# RF.net
KiCad netlist of a schematic drawn in Altium Designer
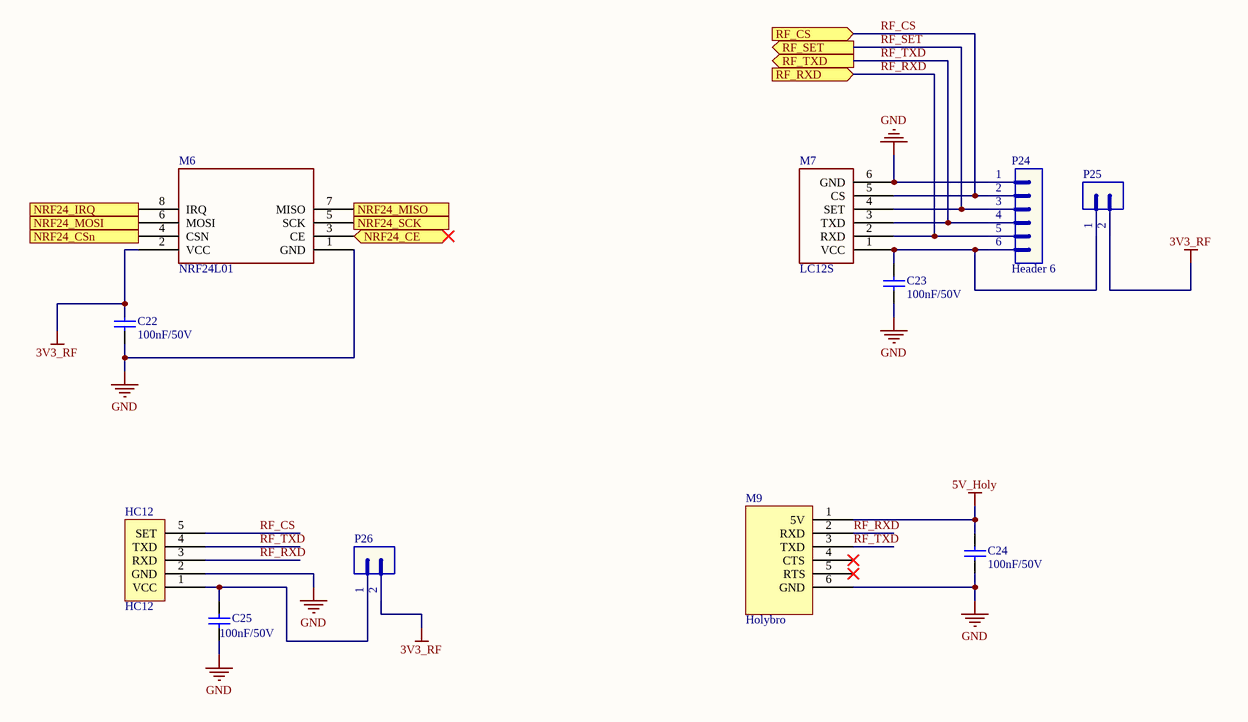
[diagram p0: RF.SchDoc]

(export (version "E")
  (design (tool "Eeschema 10.0.6"))
  (components
    (comp (ref "C22")
      (value "100nF/50V")
      (footprint "CAP-SM-0805")
      (description "CAP CER 0.1UF 50V Y5V 0805")
      (fields
        (field (name "MANUFACTURER") "Samsung Electro-Mechanics")
        (field (name "MANUFACTURER PART NUMBER") "CL21F104ZBCNNNC")
      )
      (libsource (lib "PIF_ROBOT") (part "Cap-100nF-50V-0805"))
    )
    (comp (ref "C23")
      (value "100nF/50V")
      (footprint "CAP-SM-0805")
      (description "CAP CER 0.1UF 50V Y5V 0805")
      (fields
        (field (name "MANUFACTURER") "Samsung Electro-Mechanics")
        (field (name "MANUFACTURER PART NUMBER") "CL21F104ZBCNNNC")
      )
      (libsource (lib "PIF_ROBOT") (part "Cap-100nF-50V-0805"))
    )
    (comp (ref "C24")
      (value "100nF/50V")
      (footprint "CAP-SM-0805")
      (description "CAP CER 0.1UF 50V Y5V 0805")
      (fields
        (field (name "MANUFACTURER") "Samsung Electro-Mechanics")
        (field (name "MANUFACTURER PART NUMBER") "CL21F104ZBCNNNC")
      )
      (libsource (lib "PIF_ROBOT") (part "Cap-100nF-50V-0805"))
    )
    (comp (ref "C25")
      (value "100nF/50V")
      (footprint "CAP-SM-0805")
      (description "CAP CER 0.1UF 50V Y5V 0805")
      (fields
        (field (name "MANUFACTURER") "Samsung Electro-Mechanics")
        (field (name "MANUFACTURER PART NUMBER") "CL21F104ZBCNNNC")
      )
      (libsource (lib "PIF_ROBOT") (part "Cap-100nF-50V-0805"))
    )
    (comp (ref "HC12")
      (value "HC12")
      (footprint "HC12")
      (fields (field (name "LOCAL SUPPLIER NUMBER PART") "HS000897"))
      (libsource (lib "PIF_ROBOT") (part "HC12"))
    )
    (comp (ref "M6")
      (value "NRF24L01")
      (footprint "NRF24L01")
      (libsource (lib "PIF_ROBOT") (part "NRF24L01"))
    )
    (comp (ref "M7") (value "LC12S") (footprint "LC12S") (libsource (lib "PIF_ROBOT") (part "LC12S")))
    (comp (ref "M9") (value "Holybro") (footprint "Holybro") (libsource (lib "PIF_ROBOT") (part "Holybro")))
    (comp (ref "P24")
      (value "Header 6")
      (footprint "JP6")
      (description "Header, 6-Pin")
      (fields (field (name "PUBLISHER") "Altium Limited"))
      (libsource (lib "PIF_ROBOT") (part "Header 6"))
    )
    (comp (ref "P25")
      (value "Header 2")
      (footprint "JP2")
      (description "Header, 2-Pin")
      (fields (field (name "PUBLISHER") "Altium Limited"))
      (libsource (lib "PIF_ROBOT") (part "Header 2"))
    )
    (comp (ref "P26")
      (value "Header 2")
      (footprint "JP2")
      (description "Header, 2-Pin")
      (fields (field (name "PUBLISHER") "Altium Limited"))
      (libsource (lib "PIF_ROBOT") (part "Header 2"))
    )
  )
  (nets
    (net (code "1") (name "/NRF24_CE") (class "Default")
      (node (ref "M6") (pin "3") (pinfunction "CE_3") (pintype "passive"))
    )
    (net (code "2") (name "/NRF24_CSn") (class "Default")
      (node (ref "M6") (pin "4") (pinfunction "CSN_4") (pintype "passive"))
    )
    (net (code "3") (name "/NRF24_IRQ") (class "Default")
      (node (ref "M6") (pin "8") (pinfunction "IRQ_8") (pintype "passive"))
    )
    (net (code "4") (name "/NRF24_MISO") (class "Default")
      (node (ref "M6") (pin "7") (pinfunction "MISO_7") (pintype "passive"))
    )
    (net (code "5") (name "/NRF24_MOSI") (class "Default")
      (node (ref "M6") (pin "6") (pinfunction "MOSI_6") (pintype "passive"))
    )
    (net (code "6") (name "/NRF24_SCK") (class "Default")
      (node (ref "M6") (pin "5") (pinfunction "SCK_5") (pintype "passive"))
    )
    (net (code "7") (name "/RF_CS") (class "Default")
      (node (ref "HC12") (pin "5") (pinfunction "SET_5") (pintype "passive"))
      (node (ref "M7") (pin "5") (pinfunction "CS_5") (pintype "passive"))
      (node (ref "P24") (pin "2") (pinfunction "2_2") (pintype "passive"))
    )
    (net (code "8") (name "/RF_RXD") (class "Default")
      (node (ref "HC12") (pin "3") (pinfunction "RXD_3") (pintype "passive"))
      (node (ref "M7") (pin "2") (pinfunction "RXD_2") (pintype "passive"))
      (node (ref "M9") (pin "2") (pinfunction "RXD_2") (pintype "passive"))
      (node (ref "P24") (pin "5") (pinfunction "5_5") (pintype "passive"))
    )
    (net (code "9") (name "/RF_SET") (class "Default")
      (node (ref "M7") (pin "4") (pinfunction "SET_4") (pintype "passive"))
      (node (ref "P24") (pin "3") (pinfunction "3_3") (pintype "passive"))
    )
    (net (code "10") (name "/RF_TXD") (class "Default")
      (node (ref "HC12") (pin "4") (pinfunction "TXD_4") (pintype "passive"))
      (node (ref "M7") (pin "3") (pinfunction "TXD_3") (pintype "passive"))
      (node (ref "M9") (pin "3") (pinfunction "TXD_3") (pintype "passive"))
      (node (ref "P24") (pin "4") (pinfunction "4_4") (pintype "passive"))
    )
    (net (code "11") (name "3V3_RF") (class "Default")
      (node (ref "C22") (pin "2") (pinfunction "2_2") (pintype "passive"))
      (node (ref "M6") (pin "2") (pinfunction "VCC_2") (pintype "passive"))
      (node (ref "P25") (pin "2") (pinfunction "2_2") (pintype "passive"))
      (node (ref "P26") (pin "2") (pinfunction "2_2") (pintype "passive"))
    )
    (net (code "12") (name "5V_Holy") (class "Default")
      (node (ref "C24") (pin "2") (pinfunction "2_2") (pintype "passive"))
      (node (ref "M9") (pin "1") (pinfunction "5V_1") (pintype "passive"))
    )
    (net (code "13") (name "GND") (class "Default")
      (node (ref "C22") (pin "1") (pinfunction "1_1") (pintype "passive"))
      (node (ref "C23") (pin "1") (pinfunction "1_1") (pintype "passive"))
      (node (ref "C24") (pin "1") (pinfunction "1_1") (pintype "passive"))
      (node (ref "C25") (pin "1") (pinfunction "1_1") (pintype "passive"))
      (node (ref "HC12") (pin "2") (pinfunction "GND_2") (pintype "passive"))
      (node (ref "M6") (pin "1") (pinfunction "GND_1") (pintype "passive"))
      (node (ref "M7") (pin "6") (pinfunction "GND_6") (pintype "passive"))
      (node (ref "M9") (pin "6") (pinfunction "GND_6") (pintype "passive"))
      (node (ref "P24") (pin "1") (pinfunction "1_1") (pintype "passive"))
    )
    (net (code "14") (name "Net-(HC12-VCC)") (class "Default")
      (node (ref "C25") (pin "2") (pinfunction "2_2") (pintype "passive"))
      (node (ref "HC12") (pin "1") (pinfunction "VCC_1") (pintype "passive"))
      (node (ref "P26") (pin "1") (pinfunction "1_1") (pintype "passive"))
    )
    (net (code "15") (name "Net-(M7-VCC)") (class "Default")
      (node (ref "C23") (pin "2") (pinfunction "2_2") (pintype "passive"))
      (node (ref "M7") (pin "1") (pinfunction "VCC_1") (pintype "passive"))
      (node (ref "P24") (pin "6") (pinfunction "6_6") (pintype "passive"))
      (node (ref "P25") (pin "1") (pinfunction "1_1") (pintype "passive"))
    )
    (net (code "16") (name "unconnected-(M9-CTS-Pad4)") (class "Default")
      (node (ref "M9") (pin "4") (pinfunction "CTS_4") (pintype "passive+no_connect"))
    )
    (net (code "17") (name "unconnected-(M9-RTS-Pad5)") (class "Default")
      (node (ref "M9") (pin "5") (pinfunction "RTS_5") (pintype "passive+no_connect"))
    )
  )
)
